# TissuePad_Schematic.net
KiCad netlist of a schematic drawn in Altium Designer
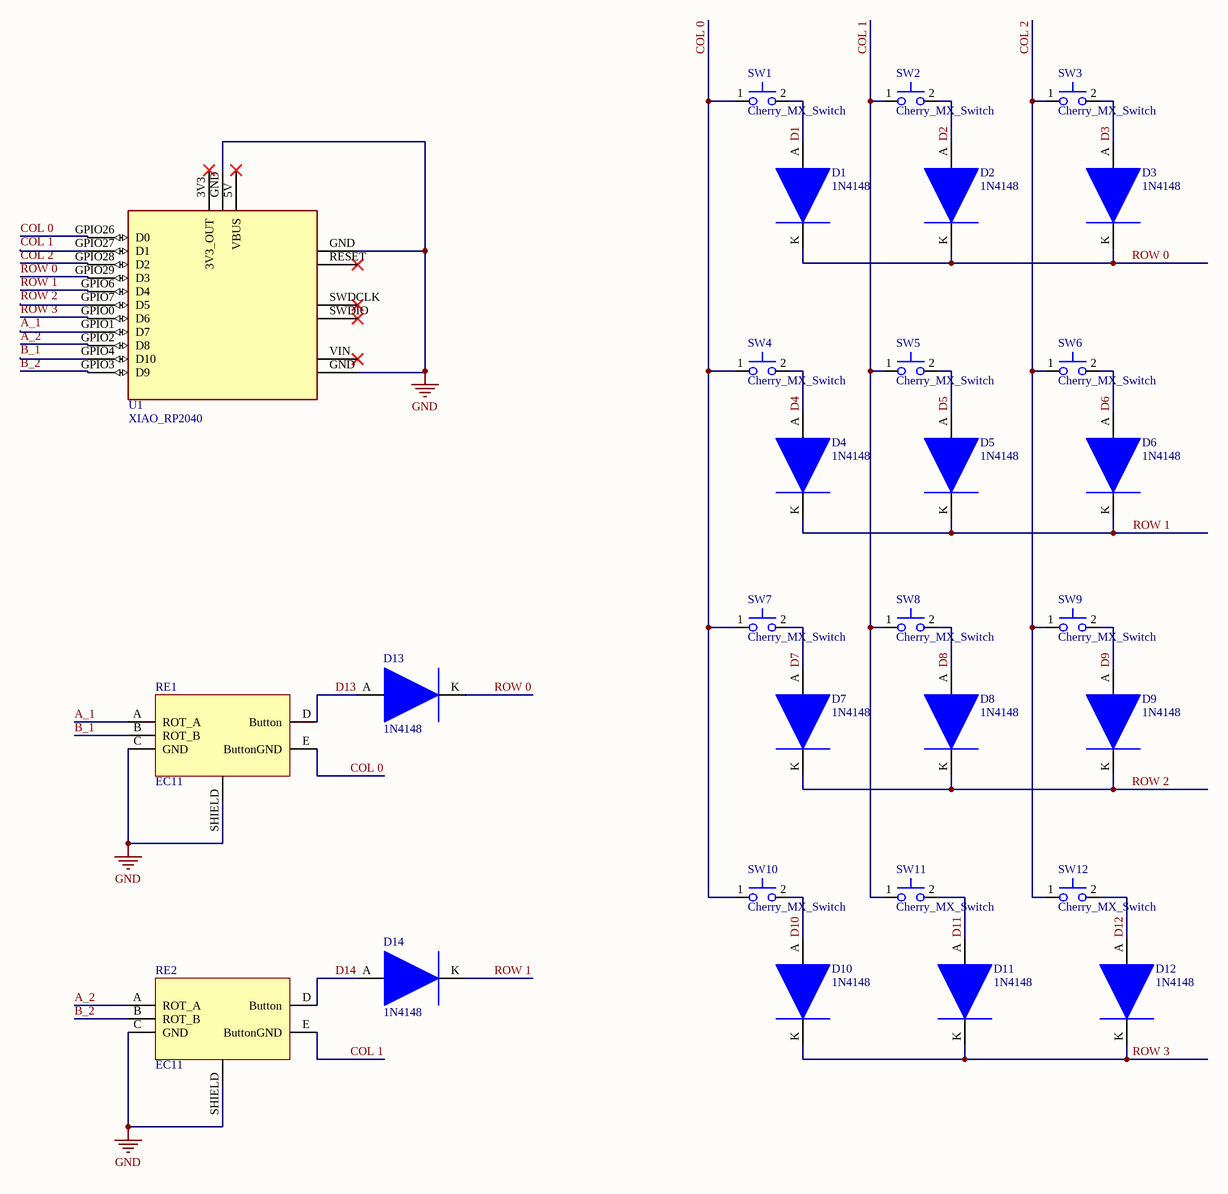
[diagram p0: TissuePad_Schematic.SchDoc]

(export (version "E")
  (design (tool "Eeschema 10.0.6"))
  (components
    (comp (ref "D1")
      (value "1N4148")
      (footprint "1N4148W")
      (description "Small Signal Fast Switching Diodes")
      (libsource (lib "TissueAltium_Schematic_Footprints") (part "1N4148"))
    )
    (comp (ref "D2")
      (value "1N4148")
      (footprint "1N4148W")
      (description "Small Signal Fast Switching Diodes")
      (libsource (lib "TissueAltium_Schematic_Footprints") (part "1N4148"))
    )
    (comp (ref "D3")
      (value "1N4148")
      (footprint "1N4148W")
      (description "Small Signal Fast Switching Diodes")
      (libsource (lib "TissueAltium_Schematic_Footprints") (part "1N4148"))
    )
    (comp (ref "D4")
      (value "1N4148")
      (footprint "1N4148W")
      (description "Small Signal Fast Switching Diodes")
      (libsource (lib "TissueAltium_Schematic_Footprints") (part "1N4148"))
    )
    (comp (ref "D5")
      (value "1N4148")
      (footprint "1N4148W")
      (description "Small Signal Fast Switching Diodes")
      (libsource (lib "TissueAltium_Schematic_Footprints") (part "1N4148"))
    )
    (comp (ref "D6")
      (value "1N4148")
      (footprint "1N4148W")
      (description "Small Signal Fast Switching Diodes")
      (libsource (lib "TissueAltium_Schematic_Footprints") (part "1N4148"))
    )
    (comp (ref "D7")
      (value "1N4148")
      (footprint "1N4148W")
      (description "Small Signal Fast Switching Diodes")
      (libsource (lib "TissueAltium_Schematic_Footprints") (part "1N4148"))
    )
    (comp (ref "D8")
      (value "1N4148")
      (footprint "1N4148W")
      (description "Small Signal Fast Switching Diodes")
      (libsource (lib "TissueAltium_Schematic_Footprints") (part "1N4148"))
    )
    (comp (ref "D9")
      (value "1N4148")
      (footprint "1N4148W")
      (description "Small Signal Fast Switching Diodes")
      (libsource (lib "TissueAltium_Schematic_Footprints") (part "1N4148"))
    )
    (comp (ref "D10")
      (value "1N4148")
      (footprint "1N4148W")
      (description "Small Signal Fast Switching Diodes")
      (libsource (lib "TissueAltium_Schematic_Footprints") (part "1N4148"))
    )
    (comp (ref "D11")
      (value "1N4148")
      (footprint "1N4148W")
      (description "Small Signal Fast Switching Diodes")
      (libsource (lib "TissueAltium_Schematic_Footprints") (part "1N4148"))
    )
    (comp (ref "D12")
      (value "1N4148")
      (footprint "1N4148W")
      (description "Small Signal Fast Switching Diodes")
      (libsource (lib "TissueAltium_Schematic_Footprints") (part "1N4148"))
    )
    (comp (ref "D13")
      (value "1N4148")
      (footprint "1N4148W")
      (description "Small Signal Fast Switching Diodes")
      (libsource (lib "TissueAltium_Schematic_Footprints") (part "1N4148"))
    )
    (comp (ref "D14")
      (value "1N4148")
      (footprint "1N4148W")
      (description "Small Signal Fast Switching Diodes")
      (libsource (lib "TissueAltium_Schematic_Footprints") (part "1N4148"))
    )
    (comp (ref "RE1")
      (value "EC11")
      (footprint "EC11E18244AU")
      (description "A Rotary Encoder with Push Button")
      (libsource (lib "TissueAltium_Schematic_Footprints") (part "EC11"))
    )
    (comp (ref "RE2")
      (value "EC11")
      (footprint "EC11E18244AU")
      (description "A Rotary Encoder with Push Button")
      (libsource (lib "TissueAltium_Schematic_Footprints") (part "EC11"))
    )
    (comp (ref "SW1")
      (value "Cherry_MX_Switch")
      (footprint "Cherry MX 2 Pin")
      (description "2 Pin Cherry MX Switch")
      (libsource (lib "TissueAltium_Schematic_Footprints") (part "Cherry_MX_Switch"))
    )
    (comp (ref "SW2")
      (value "Cherry_MX_Switch")
      (footprint "Cherry MX 2 Pin")
      (description "2 Pin Cherry MX Switch")
      (libsource (lib "TissueAltium_Schematic_Footprints") (part "Cherry_MX_Switch"))
    )
    (comp (ref "SW3")
      (value "Cherry_MX_Switch")
      (footprint "Cherry MX 2 Pin")
      (description "2 Pin Cherry MX Switch")
      (libsource (lib "TissueAltium_Schematic_Footprints") (part "Cherry_MX_Switch"))
    )
    (comp (ref "SW4")
      (value "Cherry_MX_Switch")
      (footprint "Cherry MX 2 Pin")
      (description "2 Pin Cherry MX Switch")
      (libsource (lib "TissueAltium_Schematic_Footprints") (part "Cherry_MX_Switch"))
    )
    (comp (ref "SW5")
      (value "Cherry_MX_Switch")
      (footprint "Cherry MX 2 Pin")
      (description "2 Pin Cherry MX Switch")
      (libsource (lib "TissueAltium_Schematic_Footprints") (part "Cherry_MX_Switch"))
    )
    (comp (ref "SW6")
      (value "Cherry_MX_Switch")
      (footprint "Cherry MX 2 Pin")
      (description "2 Pin Cherry MX Switch")
      (libsource (lib "TissueAltium_Schematic_Footprints") (part "Cherry_MX_Switch"))
    )
    (comp (ref "SW7")
      (value "Cherry_MX_Switch")
      (footprint "Cherry MX 2 Pin")
      (description "2 Pin Cherry MX Switch")
      (libsource (lib "TissueAltium_Schematic_Footprints") (part "Cherry_MX_Switch"))
    )
    (comp (ref "SW8")
      (value "Cherry_MX_Switch")
      (footprint "Cherry MX 2 Pin")
      (description "2 Pin Cherry MX Switch")
      (libsource (lib "TissueAltium_Schematic_Footprints") (part "Cherry_MX_Switch"))
    )
    (comp (ref "SW9")
      (value "Cherry_MX_Switch")
      (footprint "Cherry MX 2 Pin")
      (description "2 Pin Cherry MX Switch")
      (libsource (lib "TissueAltium_Schematic_Footprints") (part "Cherry_MX_Switch"))
    )
    (comp (ref "SW10")
      (value "Cherry_MX_Switch")
      (footprint "Cherry MX 2 Pin")
      (description "2 Pin Cherry MX Switch")
      (libsource (lib "TissueAltium_Schematic_Footprints") (part "Cherry_MX_Switch"))
    )
    (comp (ref "SW11")
      (value "Cherry_MX_Switch")
      (footprint "Cherry MX 2 Pin")
      (description "2 Pin Cherry MX Switch")
      (libsource (lib "TissueAltium_Schematic_Footprints") (part "Cherry_MX_Switch"))
    )
    (comp (ref "SW12")
      (value "Cherry_MX_Switch")
      (footprint "Cherry MX 2 Pin")
      (description "2 Pin Cherry MX Switch")
      (libsource (lib "TissueAltium_Schematic_Footprints") (part "Cherry_MX_Switch"))
    )
    (comp (ref "U1")
      (value "XIAO_RP2040")
      (footprint "XIAO_RP2040")
      (description "Seed Studio XIAO_RP2040 MCU Board")
      (libsource (lib "TissueAltium_Schematic_Footprints") (part "XIAO_RP2040"))
    )
  )
  (nets
    (net (code "1") (name "/A_1") (class "Default")
      (node (ref "RE1") (pin "A") (pinfunction "ROT_A_A") (pintype "passive"))
      (node (ref "U1") (pin "GPIO1") (pinfunction "D7_GPIO1") (pintype "bidirectional"))
    )
    (net (code "2") (name "/A_2") (class "Default")
      (node (ref "RE2") (pin "A") (pinfunction "ROT_A_A") (pintype "passive"))
      (node (ref "U1") (pin "GPIO2") (pinfunction "D8_GPIO2") (pintype "bidirectional"))
    )
    (net (code "3") (name "/B_1") (class "Default")
      (node (ref "RE1") (pin "B") (pinfunction "ROT_B_B") (pintype "passive"))
      (node (ref "U1") (pin "GPIO4") (pinfunction "D10_GPIO4") (pintype "bidirectional"))
    )
    (net (code "4") (name "/B_2") (class "Default")
      (node (ref "RE2") (pin "B") (pinfunction "ROT_B_B") (pintype "passive"))
      (node (ref "U1") (pin "GPIO3") (pinfunction "D9_GPIO3") (pintype "bidirectional"))
    )
    (net (code "5") (name "/COL 0") (class "Default")
      (node (ref "RE1") (pin "E") (pinfunction "ButtonGND_E") (pintype "passive"))
      (node (ref "SW1") (pin "1") (pinfunction "4_1") (pintype "passive"))
      (node (ref "SW10") (pin "1") (pinfunction "4_1") (pintype "passive"))
      (node (ref "SW4") (pin "1") (pinfunction "4_1") (pintype "passive"))
      (node (ref "SW7") (pin "1") (pinfunction "4_1") (pintype "passive"))
      (node (ref "U1") (pin "GPIO26") (pinfunction "D0_GPIO26") (pintype "bidirectional"))
    )
    (net (code "6") (name "/COL 1") (class "Default")
      (node (ref "RE2") (pin "E") (pinfunction "ButtonGND_E") (pintype "passive"))
      (node (ref "SW11") (pin "1") (pinfunction "4_1") (pintype "passive"))
      (node (ref "SW2") (pin "1") (pinfunction "4_1") (pintype "passive"))
      (node (ref "SW5") (pin "1") (pinfunction "4_1") (pintype "passive"))
      (node (ref "SW8") (pin "1") (pinfunction "4_1") (pintype "passive"))
      (node (ref "U1") (pin "GPIO27") (pinfunction "D1_GPIO27") (pintype "bidirectional"))
    )
    (net (code "7") (name "/COL 2") (class "Default")
      (node (ref "SW12") (pin "1") (pinfunction "4_1") (pintype "passive"))
      (node (ref "SW3") (pin "1") (pinfunction "4_1") (pintype "passive"))
      (node (ref "SW6") (pin "1") (pinfunction "4_1") (pintype "passive"))
      (node (ref "SW9") (pin "1") (pinfunction "4_1") (pintype "passive"))
      (node (ref "U1") (pin "GPIO28") (pinfunction "D2_GPIO28") (pintype "bidirectional"))
    )
    (net (code "8") (name "/D1") (class "Default")
      (node (ref "D1") (pin "A") (pinfunction "Anode_A") (pintype "passive"))
      (node (ref "SW1") (pin "2") (pinfunction "4_2") (pintype "passive"))
    )
    (net (code "9") (name "/D2") (class "Default")
      (node (ref "D2") (pin "A") (pinfunction "Anode_A") (pintype "passive"))
      (node (ref "SW2") (pin "2") (pinfunction "4_2") (pintype "passive"))
    )
    (net (code "10") (name "/D3") (class "Default")
      (node (ref "D3") (pin "A") (pinfunction "Anode_A") (pintype "passive"))
      (node (ref "SW3") (pin "2") (pinfunction "4_2") (pintype "passive"))
    )
    (net (code "11") (name "/D4") (class "Default")
      (node (ref "D4") (pin "A") (pinfunction "Anode_A") (pintype "passive"))
      (node (ref "SW4") (pin "2") (pinfunction "4_2") (pintype "passive"))
    )
    (net (code "12") (name "/D5") (class "Default")
      (node (ref "D5") (pin "A") (pinfunction "Anode_A") (pintype "passive"))
      (node (ref "SW5") (pin "2") (pinfunction "4_2") (pintype "passive"))
    )
    (net (code "13") (name "/D6") (class "Default")
      (node (ref "D6") (pin "A") (pinfunction "Anode_A") (pintype "passive"))
      (node (ref "SW6") (pin "2") (pinfunction "4_2") (pintype "passive"))
    )
    (net (code "14") (name "/D7") (class "Default")
      (node (ref "D7") (pin "A") (pinfunction "Anode_A") (pintype "passive"))
      (node (ref "SW7") (pin "2") (pinfunction "4_2") (pintype "passive"))
    )
    (net (code "15") (name "/D8") (class "Default")
      (node (ref "D8") (pin "A") (pinfunction "Anode_A") (pintype "passive"))
      (node (ref "SW8") (pin "2") (pinfunction "4_2") (pintype "passive"))
    )
    (net (code "16") (name "/D9") (class "Default")
      (node (ref "D9") (pin "A") (pinfunction "Anode_A") (pintype "passive"))
      (node (ref "SW9") (pin "2") (pinfunction "4_2") (pintype "passive"))
    )
    (net (code "17") (name "/D10") (class "Default")
      (node (ref "D10") (pin "A") (pinfunction "Anode_A") (pintype "passive"))
      (node (ref "SW10") (pin "2") (pinfunction "4_2") (pintype "passive"))
    )
    (net (code "18") (name "/D11") (class "Default")
      (node (ref "D11") (pin "A") (pinfunction "Anode_A") (pintype "passive"))
      (node (ref "SW11") (pin "2") (pinfunction "4_2") (pintype "passive"))
    )
    (net (code "19") (name "/D12") (class "Default")
      (node (ref "D12") (pin "A") (pinfunction "Anode_A") (pintype "passive"))
      (node (ref "SW12") (pin "2") (pinfunction "4_2") (pintype "passive"))
    )
    (net (code "20") (name "/D13") (class "Default")
      (node (ref "D13") (pin "A") (pinfunction "Anode_A") (pintype "passive"))
      (node (ref "RE1") (pin "D") (pinfunction "Button_D") (pintype "passive"))
    )
    (net (code "21") (name "/D14") (class "Default")
      (node (ref "D14") (pin "A") (pinfunction "Anode_A") (pintype "passive"))
      (node (ref "RE2") (pin "D") (pinfunction "Button_D") (pintype "passive"))
    )
    (net (code "22") (name "/ROW 0") (class "Default")
      (node (ref "D1") (pin "K") (pinfunction "Cathode_K") (pintype "passive"))
      (node (ref "D13") (pin "K") (pinfunction "Cathode_K") (pintype "passive"))
      (node (ref "D2") (pin "K") (pinfunction "Cathode_K") (pintype "passive"))
      (node (ref "D3") (pin "K") (pinfunction "Cathode_K") (pintype "passive"))
      (node (ref "U1") (pin "GPIO29") (pinfunction "D3_GPIO29") (pintype "bidirectional"))
    )
    (net (code "23") (name "/ROW 1") (class "Default")
      (node (ref "D14") (pin "K") (pinfunction "Cathode_K") (pintype "passive"))
      (node (ref "D4") (pin "K") (pinfunction "Cathode_K") (pintype "passive"))
      (node (ref "D5") (pin "K") (pinfunction "Cathode_K") (pintype "passive"))
      (node (ref "D6") (pin "K") (pinfunction "Cathode_K") (pintype "passive"))
      (node (ref "U1") (pin "GPIO6") (pinfunction "D4_GPIO6") (pintype "bidirectional"))
    )
    (net (code "24") (name "/ROW 2") (class "Default")
      (node (ref "D7") (pin "K") (pinfunction "Cathode_K") (pintype "passive"))
      (node (ref "D8") (pin "K") (pinfunction "Cathode_K") (pintype "passive"))
      (node (ref "D9") (pin "K") (pinfunction "Cathode_K") (pintype "passive"))
      (node (ref "U1") (pin "GPIO7") (pinfunction "D5_GPIO7") (pintype "bidirectional"))
    )
    (net (code "25") (name "/ROW 3") (class "Default")
      (node (ref "D10") (pin "K") (pinfunction "Cathode_K") (pintype "passive"))
      (node (ref "D11") (pin "K") (pinfunction "Cathode_K") (pintype "passive"))
      (node (ref "D12") (pin "K") (pinfunction "Cathode_K") (pintype "passive"))
      (node (ref "U1") (pin "GPIO0") (pinfunction "D6_GPIO0") (pintype "bidirectional"))
    )
    (net (code "26") (name "GND") (class "Default")
      (node (ref "RE1") (pin "C") (pinfunction "GND_C") (pintype "passive"))
      (node (ref "RE1") (pin "SHIELD") (pinfunction "6_SHIELD") (pintype "passive"))
      (node (ref "RE2") (pin "C") (pinfunction "GND_C") (pintype "passive"))
      (node (ref "RE2") (pin "SHIELD") (pinfunction "6_SHIELD") (pintype "passive"))
      (node (ref "U1") (pin "GND") (pinfunction "GND_GND") (pintype "passive"))
    )
    (net (code "27") (name "unconnected-(U1-3V3_OUT-Pad3V3)") (class "Default")
      (node (ref "U1") (pin "3V3") (pinfunction "3V3_OUT_3V3") (pintype "power_in+no_connect"))
    )
    (net (code "28") (name "unconnected-(U1-PadRESET)") (class "Default")
      (node (ref "U1") (pin "RESET") (pinfunction "RESET_RESET") (pintype "passive+no_connect"))
    )
    (net (code "29") (name "unconnected-(U1-PadSWDCLK)") (class "Default")
      (node (ref "U1") (pin "SWDCLK") (pinfunction "SWDCLK_SWDCLK") (pintype "passive+no_connect"))
    )
    (net (code "30") (name "unconnected-(U1-PadSWDIO)") (class "Default")
      (node (ref "U1") (pin "SWDIO") (pinfunction "SWDIO_SWDIO") (pintype "passive+no_connect"))
    )
    (net (code "31") (name "unconnected-(U1-PadVIN)") (class "Default")
      (node (ref "U1") (pin "VIN") (pinfunction "VIN_VIN") (pintype "passive+no_connect"))
    )
    (net (code "32") (name "unconnected-(U1-VBUS-Pad5V)") (class "Default")
      (node (ref "U1") (pin "5V") (pinfunction "VBUS_5V") (pintype "power_in+no_connect"))
    )
  )
)
